# FunctionGeneratorGateDriver.net
KiCad netlist of a schematic drawn in EAGLE
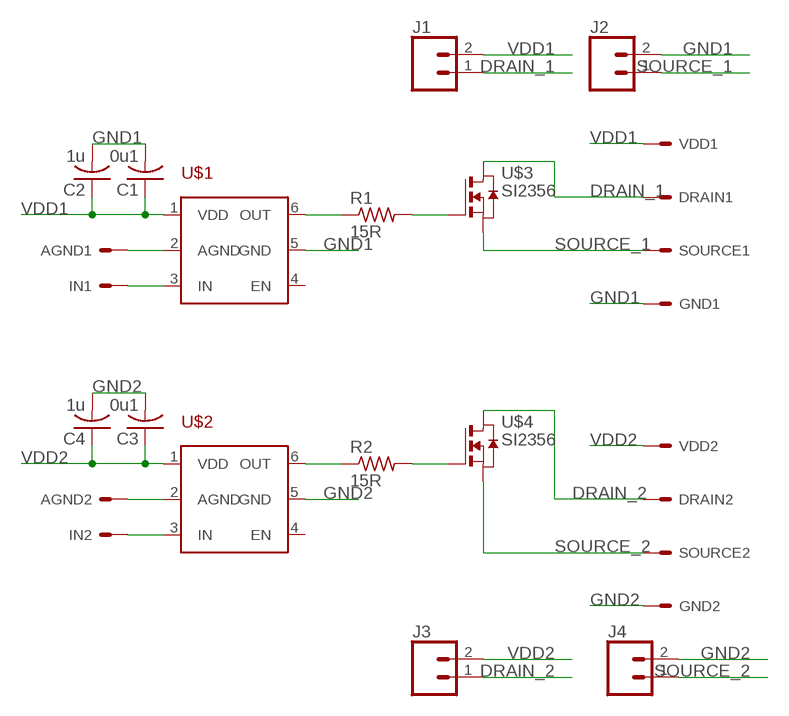
[diagram p0: schematic, sheet 1]

(export (version "E")
  (design (tool "Eeschema 10.0.6"))
  (components
    (comp (ref "AGND1")
      (value "P1X1")
      (footprint "eagle-import:1X01")
      (libsource (lib "eagle-import") (part "P1X1"))
    )
    (comp (ref "AGND2")
      (value "P1X1")
      (footprint "eagle-import:1X01")
      (libsource (lib "eagle-import") (part "P1X1"))
    )
    (comp (ref "C1")
      (value "0u1")
      (footprint "eagle-import:C1206")
      (libsource (lib "eagle-import") (part "C-USC1206"))
    )
    (comp (ref "C2")
      (value "1u")
      (footprint "eagle-import:C1206")
      (libsource (lib "eagle-import") (part "C-USC1206"))
    )
    (comp (ref "C3")
      (value "0u1")
      (footprint "eagle-import:C1206")
      (libsource (lib "eagle-import") (part "C-USC1206"))
    )
    (comp (ref "C4")
      (value "1u")
      (footprint "eagle-import:C1206")
      (libsource (lib "eagle-import") (part "C-USC1206"))
    )
    (comp (ref "DRAIN1")
      (value "P1X1")
      (footprint "eagle-import:1X01")
      (libsource (lib "eagle-import") (part "P1X1"))
    )
    (comp (ref "DRAIN2")
      (value "P1X1")
      (footprint "eagle-import:1X01")
      (libsource (lib "eagle-import") (part "P1X1"))
    )
    (comp (ref "GND1")
      (value "P1X1")
      (footprint "eagle-import:1X01")
      (libsource (lib "eagle-import") (part "P1X1"))
    )
    (comp (ref "GND2")
      (value "P1X1")
      (footprint "eagle-import:1X01")
      (libsource (lib "eagle-import") (part "P1X1"))
    )
    (comp (ref "IN1")
      (value "P1X1")
      (footprint "eagle-import:1X01")
      (libsource (lib "eagle-import") (part "P1X1"))
    )
    (comp (ref "IN2")
      (value "P1X1")
      (footprint "eagle-import:1X01")
      (libsource (lib "eagle-import") (part "P1X1"))
    )
    (comp (ref "J1")
      (value "CONN_02")
      (footprint "eagle-import:1X02")
      (libsource (lib "eagle-import") (part "CONN_02"))
    )
    (comp (ref "J2")
      (value "CONN_02")
      (footprint "eagle-import:1X02")
      (libsource (lib "eagle-import") (part "CONN_02"))
    )
    (comp (ref "J3")
      (value "CONN_02")
      (footprint "eagle-import:1X02")
      (libsource (lib "eagle-import") (part "CONN_02"))
    )
    (comp (ref "J4")
      (value "CONN_02")
      (footprint "eagle-import:1X02")
      (libsource (lib "eagle-import") (part "CONN_02"))
    )
    (comp (ref "R1")
      (value "15R")
      (footprint "eagle-import:R1206")
      (libsource (lib "eagle-import") (part "R-US_R1206"))
    )
    (comp (ref "R2")
      (value "15R")
      (footprint "eagle-import:R1206")
      (libsource (lib "eagle-import") (part "R-US_R1206"))
    )
    (comp (ref "SOURCE1")
      (value "P1X1")
      (footprint "eagle-import:1X01")
      (libsource (lib "eagle-import") (part "P1X1"))
    )
    (comp (ref "SOURCE2")
      (value "P1X1")
      (footprint "eagle-import:1X01")
      (libsource (lib "eagle-import") (part "P1X1"))
    )
    (comp (ref "U$1")
      (value "MCP14A0152")
      (footprint "eagle-import:SOT95P270X150-6")
      (libsource (lib "eagle-import") (part "MCP14A0152"))
    )
    (comp (ref "U$2")
      (value "MCP14A0152")
      (footprint "eagle-import:SOT95P270X150-6")
      (libsource (lib "eagle-import") (part "MCP14A0152"))
    )
    (comp (ref "U$3")
      (value "SI2356")
      (footprint "eagle-import:SOT95P237X120-3")
      (libsource (lib "eagle-import") (part "SI2356"))
    )
    (comp (ref "U$4")
      (value "SI2356")
      (footprint "eagle-import:SOT95P237X120-3")
      (libsource (lib "eagle-import") (part "SI2356"))
    )
    (comp (ref "VDD1")
      (value "P1X1")
      (footprint "eagle-import:1X01")
      (libsource (lib "eagle-import") (part "P1X1"))
    )
    (comp (ref "VDD2")
      (value "P1X1")
      (footprint "eagle-import:1X01")
      (libsource (lib "eagle-import") (part "P1X1"))
    )
  )
  (nets
    (net (code "1") (name "/DRAIN_1") (class "Default")
      (node (ref "DRAIN1") (pin "1") (pinfunction "MS_1") (pintype "passive"))
      (node (ref "J1") (pin "1") (pinfunction "1_1") (pintype "passive"))
      (node (ref "U$3") (pin "3") (pinfunction "D_3") (pintype "passive"))
    )
    (net (code "2") (name "/DRAIN_2") (class "Default")
      (node (ref "DRAIN2") (pin "1") (pinfunction "MS_1") (pintype "passive"))
      (node (ref "J3") (pin "1") (pinfunction "1_1") (pintype "passive"))
      (node (ref "U$4") (pin "3") (pinfunction "D_3") (pintype "passive"))
    )
    (net (code "3") (name "/GND1") (class "Default")
      (node (ref "C1") (pin "2") (pinfunction "2_2") (pintype "passive"))
      (node (ref "C2") (pin "2") (pinfunction "2_2") (pintype "passive"))
      (node (ref "GND1") (pin "1") (pinfunction "MS_1") (pintype "passive"))
      (node (ref "J2") (pin "2") (pinfunction "2_2") (pintype "passive"))
      (node (ref "U$1") (pin "5") (pinfunction "GND_5") (pintype "bidirectional"))
    )
    (net (code "4") (name "/GND2") (class "Default")
      (node (ref "C3") (pin "2") (pinfunction "2_2") (pintype "passive"))
      (node (ref "C4") (pin "2") (pinfunction "2_2") (pintype "passive"))
      (node (ref "GND2") (pin "1") (pinfunction "MS_1") (pintype "passive"))
      (node (ref "J4") (pin "2") (pinfunction "2_2") (pintype "passive"))
      (node (ref "U$2") (pin "5") (pinfunction "GND_5") (pintype "bidirectional"))
    )
    (net (code "5") (name "/SOURCE_1") (class "Default")
      (node (ref "J2") (pin "1") (pinfunction "1_1") (pintype "passive"))
      (node (ref "SOURCE1") (pin "1") (pinfunction "MS_1") (pintype "passive"))
      (node (ref "U$3") (pin "2") (pinfunction "S_2") (pintype "passive"))
    )
    (net (code "6") (name "/SOURCE_2") (class "Default")
      (node (ref "J4") (pin "1") (pinfunction "1_1") (pintype "passive"))
      (node (ref "SOURCE2") (pin "1") (pinfunction "MS_1") (pintype "passive"))
      (node (ref "U$4") (pin "2") (pinfunction "S_2") (pintype "passive"))
    )
    (net (code "7") (name "/VDD1") (class "Default")
      (node (ref "C1") (pin "1") (pinfunction "1_1") (pintype "passive"))
      (node (ref "C2") (pin "1") (pinfunction "1_1") (pintype "passive"))
      (node (ref "J1") (pin "2") (pinfunction "2_2") (pintype "passive"))
      (node (ref "U$1") (pin "1") (pinfunction "VDD_1") (pintype "bidirectional"))
      (node (ref "VDD1") (pin "1") (pinfunction "MS_1") (pintype "passive"))
    )
    (net (code "8") (name "/VDD2") (class "Default")
      (node (ref "C3") (pin "1") (pinfunction "1_1") (pintype "passive"))
      (node (ref "C4") (pin "1") (pinfunction "1_1") (pintype "passive"))
      (node (ref "J3") (pin "2") (pinfunction "2_2") (pintype "passive"))
      (node (ref "U$2") (pin "1") (pinfunction "VDD_1") (pintype "bidirectional"))
      (node (ref "VDD2") (pin "1") (pinfunction "MS_1") (pintype "passive"))
    )
    (net (code "9") (name "Net-(AGND1-MS)") (class "Default")
      (node (ref "AGND1") (pin "1") (pinfunction "MS_1") (pintype "passive"))
      (node (ref "U$1") (pin "2") (pinfunction "AGND_2") (pintype "bidirectional"))
    )
    (net (code "10") (name "Net-(AGND2-MS)") (class "Default")
      (node (ref "AGND2") (pin "1") (pinfunction "MS_1") (pintype "passive"))
      (node (ref "U$2") (pin "2") (pinfunction "AGND_2") (pintype "bidirectional"))
    )
    (net (code "11") (name "Net-(IN1-MS)") (class "Default")
      (node (ref "IN1") (pin "1") (pinfunction "MS_1") (pintype "passive"))
      (node (ref "U$1") (pin "3") (pinfunction "IN_3") (pintype "bidirectional"))
    )
    (net (code "12") (name "Net-(IN2-MS)") (class "Default")
      (node (ref "IN2") (pin "1") (pinfunction "MS_1") (pintype "passive"))
      (node (ref "U$2") (pin "3") (pinfunction "IN_3") (pintype "bidirectional"))
    )
    (net (code "13") (name "Net-(U$1-OUT)") (class "Default")
      (node (ref "R1") (pin "1") (pinfunction "1_1") (pintype "passive"))
      (node (ref "U$1") (pin "6") (pinfunction "OUT_6") (pintype "bidirectional"))
    )
    (net (code "14") (name "Net-(U$2-OUT)") (class "Default")
      (node (ref "R2") (pin "1") (pinfunction "1_1") (pintype "passive"))
      (node (ref "U$2") (pin "6") (pinfunction "OUT_6") (pintype "bidirectional"))
    )
    (net (code "15") (name "Net-(U$3-G)") (class "Default")
      (node (ref "R1") (pin "2") (pinfunction "2_2") (pintype "passive"))
      (node (ref "U$3") (pin "1") (pinfunction "G_1") (pintype "passive"))
    )
    (net (code "16") (name "Net-(U$4-G)") (class "Default")
      (node (ref "R2") (pin "2") (pinfunction "2_2") (pintype "passive"))
      (node (ref "U$4") (pin "1") (pinfunction "G_1") (pintype "passive"))
    )
    (net (code "17") (name "unconnected-(U$1-EN-Pad4)") (class "Default")
      (node (ref "U$1") (pin "4") (pinfunction "EN_4") (pintype "bidirectional"))
    )
    (net (code "18") (name "unconnected-(U$2-EN-Pad4)") (class "Default")
      (node (ref "U$2") (pin "4") (pinfunction "EN_4") (pintype "bidirectional"))
    )
  )
)
